# Board-PWM.net
KiCad netlist of a schematic drawn in Altium Designer
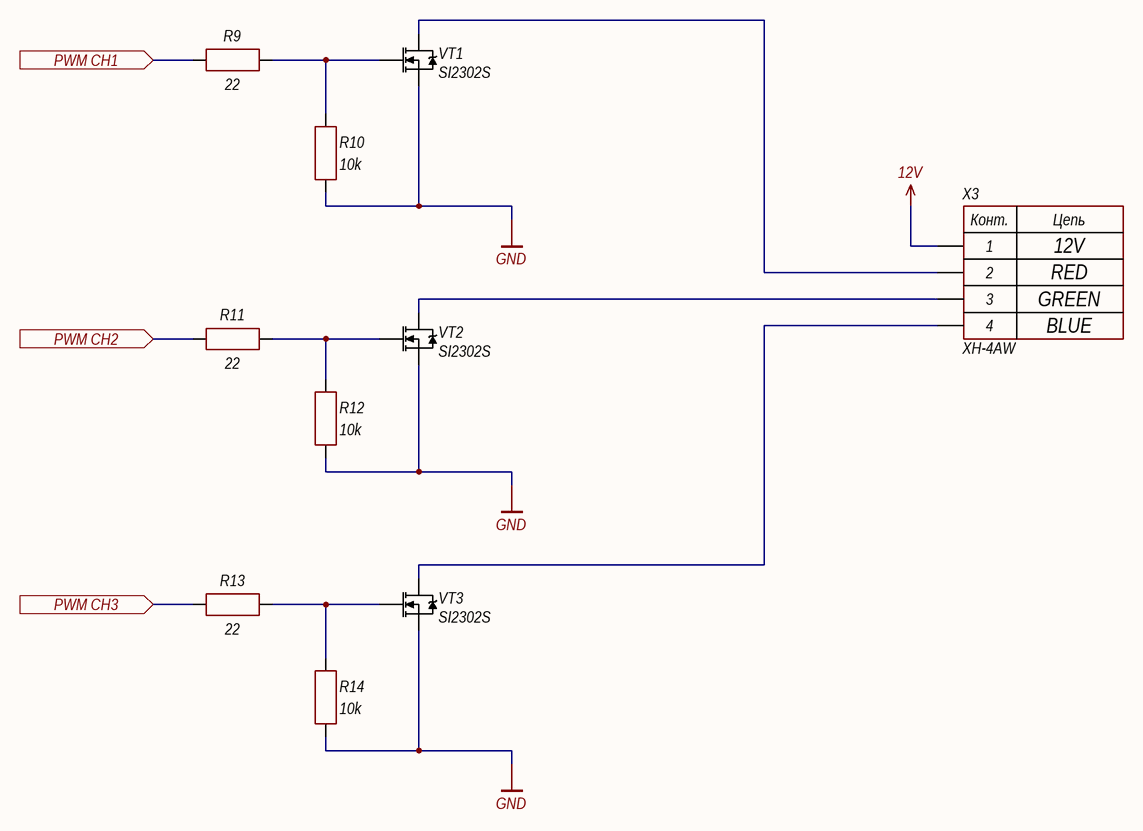
[diagram p0: Board-PWM.SchDoc]

(export (version "E")
  (design (tool "Eeschema 10.0.6"))
  (components
    (comp (ref "R9")
      (value "22")
      (footprint "CH0402R")
      (fields (field (name "MANUFACTURER") "YAGEO"))
      (libsource (lib "") (part "Resistor_1"))
    )
    (comp (ref "R10")
      (value "10k")
      (footprint "CH0402R")
      (fields (field (name "MANUFACTURER") "Uniroyal Elec"))
      (libsource (lib "Discrete") (part "Resistor"))
    )
    (comp (ref "R11")
      (value "22")
      (footprint "CH0402R")
      (fields (field (name "MANUFACTURER") "YAGEO"))
      (libsource (lib "") (part "Resistor_1"))
    )
    (comp (ref "R12")
      (value "10k")
      (footprint "CH0402R")
      (fields (field (name "MANUFACTURER") "Uniroyal Elec"))
      (libsource (lib "Discrete") (part "Resistor"))
    )
    (comp (ref "R13")
      (value "22")
      (footprint "CH0402R")
      (fields (field (name "MANUFACTURER") "YAGEO"))
      (libsource (lib "") (part "Resistor_1"))
    )
    (comp (ref "R14")
      (value "10k")
      (footprint "CH0402R")
      (fields (field (name "MANUFACTURER") "Uniroyal Elec"))
      (libsource (lib "Discrete") (part "Resistor"))
    )
    (comp (ref "VT1")
      (value "SI2302S")
      (footprint "SOT23_123")
      (description "Mosfet")
      (fields (field (name "MANUFACTURER") "Microdiode Electronics"))
      (libsource (lib "Transistor") (part "N-chanel"))
    )
    (comp (ref "VT2")
      (value "SI2302S")
      (footprint "SOT23_123")
      (description "Mosfet")
      (fields (field (name "MANUFACTURER") "Microdiode Electronics"))
      (libsource (lib "Transistor") (part "N-chanel"))
    )
    (comp (ref "VT3")
      (value "SI2302S")
      (footprint "SOT23_123")
      (description "Mosfet")
      (fields (field (name "MANUFACTURER") "Microdiode Electronics"))
      (libsource (lib "Transistor") (part "N-chanel"))
    )
    (comp (ref "X3")
      (value "XH-4AW")
      (footprint "CON: XH-4AW")
      (libsource (lib "Connectors") (part "4-Connector"))
    )
  )
  (nets
    (net (code "1") (name "/PWM CH1") (class "Default")
      (node (ref "R9") (pin "1") (pinfunction "1_1") (pintype "passive"))
    )
    (net (code "2") (name "/PWM CH2") (class "Default")
      (node (ref "R11") (pin "1") (pinfunction "1_1") (pintype "passive"))
    )
    (net (code "3") (name "/PWM CH3") (class "Default")
      (node (ref "R13") (pin "1") (pinfunction "1_1") (pintype "passive"))
    )
    (net (code "4") (name "12V") (class "Default")
      (node (ref "X3") (pin "1") (pinfunction "1_1") (pintype "passive"))
    )
    (net (code "5") (name "GND") (class "Default")
      (node (ref "R10") (pin "1") (pinfunction "1_1") (pintype "passive"))
      (node (ref "R12") (pin "1") (pinfunction "1_1") (pintype "passive"))
      (node (ref "R14") (pin "1") (pinfunction "1_1") (pintype "passive"))
      (node (ref "VT1") (pin "3") (pinfunction "S_3") (pintype "passive"))
      (node (ref "VT2") (pin "3") (pinfunction "S_3") (pintype "passive"))
      (node (ref "VT3") (pin "3") (pinfunction "S_3") (pintype "passive"))
    )
    (net (code "6") (name "Net-(VT1-D)") (class "Default")
      (node (ref "VT1") (pin "2") (pinfunction "D_2") (pintype "passive"))
      (node (ref "X3") (pin "2") (pinfunction "2_2") (pintype "passive"))
    )
    (net (code "7") (name "Net-(VT1-G)") (class "Default")
      (node (ref "R10") (pin "2") (pinfunction "2_2") (pintype "passive"))
      (node (ref "R9") (pin "2") (pinfunction "2_2") (pintype "passive"))
      (node (ref "VT1") (pin "1") (pinfunction "G_1") (pintype "passive"))
    )
    (net (code "8") (name "Net-(VT2-D)") (class "Default")
      (node (ref "VT2") (pin "2") (pinfunction "D_2") (pintype "passive"))
      (node (ref "X3") (pin "3") (pinfunction "3_3") (pintype "passive"))
    )
    (net (code "9") (name "Net-(VT2-G)") (class "Default")
      (node (ref "R11") (pin "2") (pinfunction "2_2") (pintype "passive"))
      (node (ref "R12") (pin "2") (pinfunction "2_2") (pintype "passive"))
      (node (ref "VT2") (pin "1") (pinfunction "G_1") (pintype "passive"))
    )
    (net (code "10") (name "Net-(VT3-D)") (class "Default")
      (node (ref "VT3") (pin "2") (pinfunction "D_2") (pintype "passive"))
      (node (ref "X3") (pin "4") (pinfunction "4_4") (pintype "passive"))
    )
    (net (code "11") (name "Net-(VT3-G)") (class "Default")
      (node (ref "R13") (pin "2") (pinfunction "2_2") (pintype "passive"))
      (node (ref "R14") (pin "2") (pinfunction "2_2") (pintype "passive"))
      (node (ref "VT3") (pin "1") (pinfunction "G_1") (pintype "passive"))
    )
  )
)
